# fpgaPower.net
KiCad netlist of a schematic drawn in Altium Designer
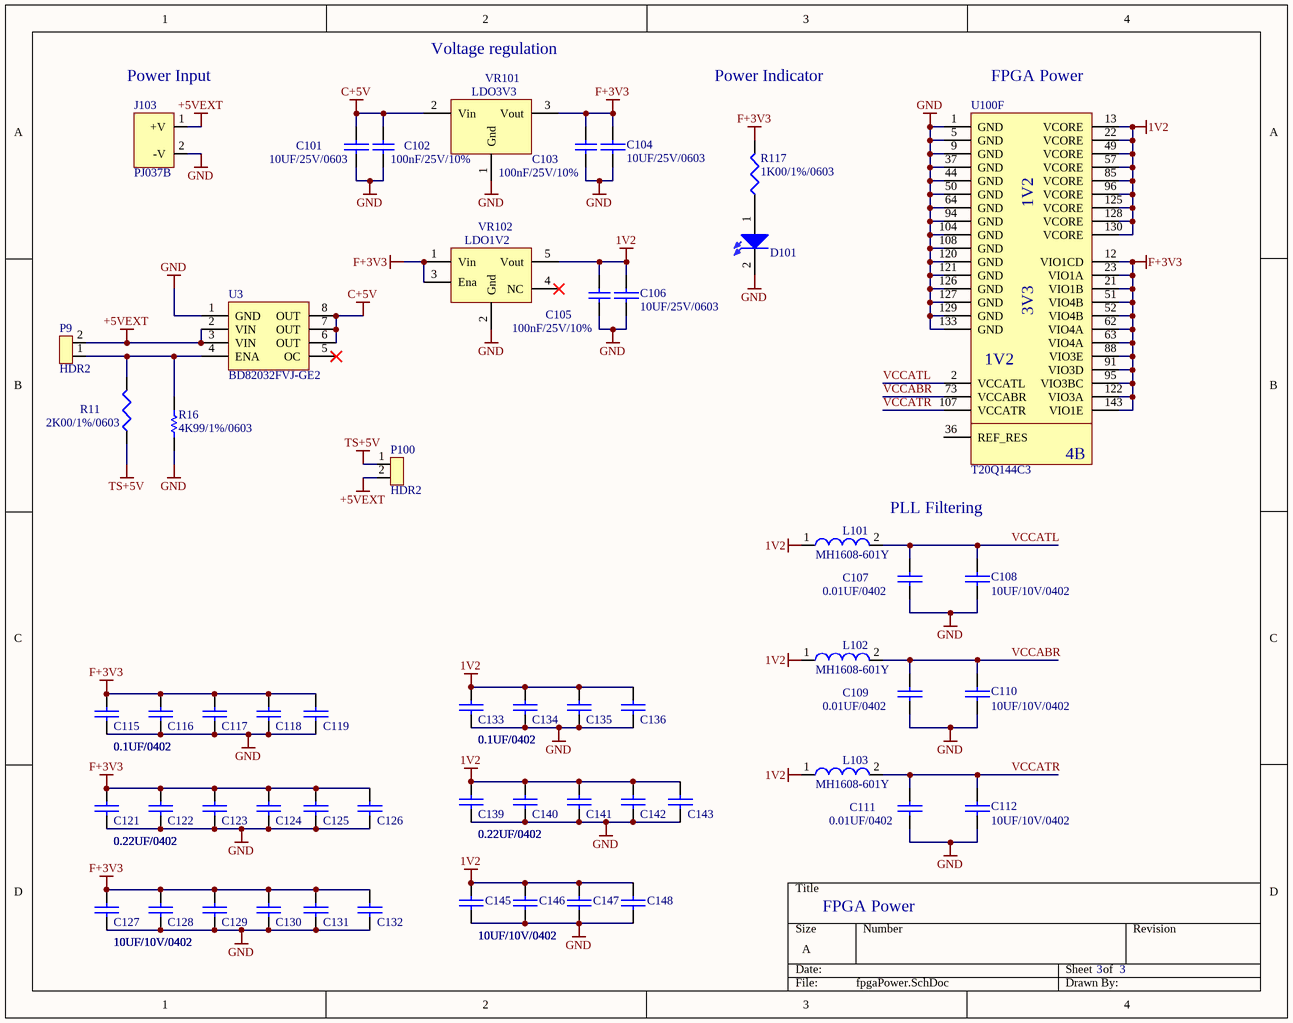
[diagram p0: fpgaPower.SchDoc]

(export (version "E")
  (design (tool "Eeschema 10.0.6"))
  (components
    (comp (ref "C101")
      (value "10UF/25V/0603")
      (footprint "0603")
      (description "10 µF ±20% 25V Ceramic Capacitor X5R 0603 (1608 Metric)")
      (fields (field (name "MFG") "Samsung"))
      (libsource (lib "Capacitors") (part "10UF/25V/0603"))
    )
    (comp (ref "C102")
      (value "100nF/25V/10%")
      (footprint "MY0603")
      (description "0.1µF ±10% 25V Ceramic Capacitor X7R 0603 (1608 Metric)")
      (fields (field (name "MFG") "AVX"))
      (libsource (lib "Capacitors") (part "CAP100NF25V"))
    )
    (comp (ref "C103")
      (value "100nF/25V/10%")
      (footprint "MY0603")
      (description "0.1µF ±10% 25V Ceramic Capacitor X7R 0603 (1608 Metric)")
      (fields (field (name "MFG") "AVX"))
      (libsource (lib "Capacitors") (part "CAP100NF25V"))
    )
    (comp (ref "C104")
      (value "10UF/25V/0603")
      (footprint "0603")
      (description "10 µF ±20% 25V Ceramic Capacitor X5R 0603 (1608 Metric)")
      (fields (field (name "MFG") "Samsung"))
      (libsource (lib "Capacitors") (part "10UF/25V/0603"))
    )
    (comp (ref "C105")
      (value "100nF/25V/10%")
      (footprint "MY0603")
      (description "0.1µF ±10% 25V Ceramic Capacitor X7R 0603 (1608 Metric)")
      (fields (field (name "MFG") "AVX"))
      (libsource (lib "Capacitors") (part "CAP100NF25V"))
    )
    (comp (ref "C106")
      (value "10UF/25V/0603")
      (footprint "0603")
      (description "10 µF ±20% 25V Ceramic Capacitor X5R 0603 (1608 Metric)")
      (fields (field (name "MFG") "Samsung"))
      (libsource (lib "Capacitors") (part "10UF/25V/0603"))
    )
    (comp (ref "C107")
      (value "0.01UF/0402")
      (footprint "0402")
      (description "±10% 16V Ceramic Capacitor X7R 0402 (1005 Metric)")
      (fields (field (name "MFG") "Cal-Chip"))
      (libsource (lib "Capacitors") (part "0.01UF/16vV/0402"))
    )
    (comp (ref "C108")
      (value "10UF/10V/0402")
      (footprint "0402")
      (description "±20% 10V Ceramic Capacitor X5R 0402 (1005 Metric)")
      (fields (field (name "MFG") "Samsung"))
      (libsource (lib "Capacitors") (part "10UF/10V/0402"))
    )
    (comp (ref "C109")
      (value "0.01UF/0402")
      (footprint "0402")
      (description "±10% 16V Ceramic Capacitor X7R 0402 (1005 Metric)")
      (fields (field (name "MFG") "Cal-Chip"))
      (libsource (lib "Capacitors") (part "0.01UF/16vV/0402"))
    )
    (comp (ref "C110")
      (value "10UF/10V/0402")
      (footprint "0402")
      (description "±20% 10V Ceramic Capacitor X5R 0402 (1005 Metric)")
      (fields (field (name "MFG") "Samsung"))
      (libsource (lib "Capacitors") (part "10UF/10V/0402"))
    )
    (comp (ref "C111")
      (value "0.01UF/0402")
      (footprint "0402")
      (description "±10% 16V Ceramic Capacitor X7R 0402 (1005 Metric)")
      (fields (field (name "MFG") "Cal-Chip"))
      (libsource (lib "Capacitors") (part "0.01UF/16vV/0402"))
    )
    (comp (ref "C112")
      (value "10UF/10V/0402")
      (footprint "0402")
      (description "±20% 10V Ceramic Capacitor X5R 0402 (1005 Metric)")
      (fields (field (name "MFG") "Samsung"))
      (libsource (lib "Capacitors") (part "10UF/10V/0402"))
    )
    (comp (ref "C115")
      (value "0.1UF/0402")
      (footprint "0402")
      (description "±10% 16V Ceramic Capacitor X7R 0402 (1005 Metric)")
      (fields (field (name "MFG") "TDK"))
      (libsource (lib "Capacitors") (part "0.1UF/16v/0402"))
    )
    (comp (ref "C116")
      (value "0.1UF/0402")
      (footprint "0402")
      (description "±10% 16V Ceramic Capacitor X7R 0402 (1005 Metric)")
      (fields (field (name "MFG") "TDK"))
      (libsource (lib "Capacitors") (part "0.1UF/16v/0402"))
    )
    (comp (ref "C117")
      (value "0.1UF/0402")
      (footprint "0402")
      (description "±10% 16V Ceramic Capacitor X7R 0402 (1005 Metric)")
      (fields (field (name "MFG") "TDK"))
      (libsource (lib "Capacitors") (part "0.1UF/16v/0402"))
    )
    (comp (ref "C118")
      (value "0.1UF/0402")
      (footprint "0402")
      (description "±10% 16V Ceramic Capacitor X7R 0402 (1005 Metric)")
      (fields (field (name "MFG") "TDK"))
      (libsource (lib "Capacitors") (part "0.1UF/16v/0402"))
    )
    (comp (ref "C119")
      (value "0.1UF/0402")
      (footprint "0402")
      (description "±10% 16V Ceramic Capacitor X7R 0402 (1005 Metric)")
      (fields (field (name "MFG") "TDK"))
      (libsource (lib "Capacitors") (part "0.1UF/16v/0402"))
    )
    (comp (ref "C121")
      (value "0.22UF/0402")
      (footprint "0402")
      (description "0.22 µF ±10% 25V Ceramic Capacitor X5R 0402 (1005 Metric)")
      (fields (field (name "MFG") "Yaego"))
      (libsource (lib "Capacitors") (part "0.22UF/0402"))
    )
    (comp (ref "C122")
      (value "0.22UF/0402")
      (footprint "0402")
      (description "0.22 µF ±10% 25V Ceramic Capacitor X5R 0402 (1005 Metric)")
      (fields (field (name "MFG") "Yaego"))
      (libsource (lib "Capacitors") (part "0.22UF/0402"))
    )
    (comp (ref "C123")
      (value "0.22UF/0402")
      (footprint "0402")
      (description "0.22 µF ±10% 25V Ceramic Capacitor X5R 0402 (1005 Metric)")
      (fields (field (name "MFG") "Yaego"))
      (libsource (lib "Capacitors") (part "0.22UF/0402"))
    )
    (comp (ref "C124")
      (value "0.22UF/0402")
      (footprint "0402")
      (description "0.22 µF ±10% 25V Ceramic Capacitor X5R 0402 (1005 Metric)")
      (fields (field (name "MFG") "Yaego"))
      (libsource (lib "Capacitors") (part "0.22UF/0402"))
    )
    (comp (ref "C125")
      (value "0.22UF/0402")
      (footprint "0402")
      (description "0.22 µF ±10% 25V Ceramic Capacitor X5R 0402 (1005 Metric)")
      (fields (field (name "MFG") "Yaego"))
      (libsource (lib "Capacitors") (part "0.22UF/0402"))
    )
    (comp (ref "C126")
      (value "0.22UF/0402")
      (footprint "0402")
      (description "0.22 µF ±10% 25V Ceramic Capacitor X5R 0402 (1005 Metric)")
      (fields (field (name "MFG") "Yaego"))
      (libsource (lib "Capacitors") (part "0.22UF/0402"))
    )
    (comp (ref "C127")
      (value "10UF/10V/0402")
      (footprint "0402")
      (description "±20% 10V Ceramic Capacitor X5R 0402 (1005 Metric)")
      (fields (field (name "MFG") "Samsung"))
      (libsource (lib "Capacitors") (part "10UF/10V/0402"))
    )
    (comp (ref "C128")
      (value "10UF/10V/0402")
      (footprint "0402")
      (description "±20% 10V Ceramic Capacitor X5R 0402 (1005 Metric)")
      (fields (field (name "MFG") "Samsung"))
      (libsource (lib "Capacitors") (part "10UF/10V/0402"))
    )
    (comp (ref "C129")
      (value "10UF/10V/0402")
      (footprint "0402")
      (description "±20% 10V Ceramic Capacitor X5R 0402 (1005 Metric)")
      (fields (field (name "MFG") "Samsung"))
      (libsource (lib "Capacitors") (part "10UF/10V/0402"))
    )
    (comp (ref "C130")
      (value "10UF/10V/0402")
      (footprint "0402")
      (description "±20% 10V Ceramic Capacitor X5R 0402 (1005 Metric)")
      (fields (field (name "MFG") "Samsung"))
      (libsource (lib "Capacitors") (part "10UF/10V/0402"))
    )
    (comp (ref "C131")
      (value "10UF/10V/0402")
      (footprint "0402")
      (description "±20% 10V Ceramic Capacitor X5R 0402 (1005 Metric)")
      (fields (field (name "MFG") "Samsung"))
      (libsource (lib "Capacitors") (part "10UF/10V/0402"))
    )
    (comp (ref "C132")
      (value "10UF/10V/0402")
      (footprint "0402")
      (description "±20% 10V Ceramic Capacitor X5R 0402 (1005 Metric)")
      (fields (field (name "MFG") "Samsung"))
      (libsource (lib "Capacitors") (part "10UF/10V/0402"))
    )
    (comp (ref "C133")
      (value "0.1UF/0402")
      (footprint "0402")
      (description "±10% 16V Ceramic Capacitor X7R 0402 (1005 Metric)")
      (fields (field (name "MFG") "TDK"))
      (libsource (lib "Capacitors") (part "0.1UF/16v/0402"))
    )
    (comp (ref "C134")
      (value "0.1UF/0402")
      (footprint "0402")
      (description "±10% 16V Ceramic Capacitor X7R 0402 (1005 Metric)")
      (fields (field (name "MFG") "TDK"))
      (libsource (lib "Capacitors") (part "0.1UF/16v/0402"))
    )
    (comp (ref "C135")
      (value "0.1UF/0402")
      (footprint "0402")
      (description "±10% 16V Ceramic Capacitor X7R 0402 (1005 Metric)")
      (fields (field (name "MFG") "TDK"))
      (libsource (lib "Capacitors") (part "0.1UF/16v/0402"))
    )
    (comp (ref "C136")
      (value "0.1UF/0402")
      (footprint "0402")
      (description "±10% 16V Ceramic Capacitor X7R 0402 (1005 Metric)")
      (fields (field (name "MFG") "TDK"))
      (libsource (lib "Capacitors") (part "0.1UF/16v/0402"))
    )
    (comp (ref "C139")
      (value "0.22UF/0402")
      (footprint "0402")
      (description "0.22 µF ±10% 25V Ceramic Capacitor X5R 0402 (1005 Metric)")
      (fields (field (name "MFG") "Yaego"))
      (libsource (lib "Capacitors") (part "0.22UF/0402"))
    )
    (comp (ref "C140")
      (value "0.22UF/0402")
      (footprint "0402")
      (description "0.22 µF ±10% 25V Ceramic Capacitor X5R 0402 (1005 Metric)")
      (fields (field (name "MFG") "Yaego"))
      (libsource (lib "Capacitors") (part "0.22UF/0402"))
    )
    (comp (ref "C141")
      (value "0.22UF/0402")
      (footprint "0402")
      (description "0.22 µF ±10% 25V Ceramic Capacitor X5R 0402 (1005 Metric)")
      (fields (field (name "MFG") "Yaego"))
      (libsource (lib "Capacitors") (part "0.22UF/0402"))
    )
    (comp (ref "C142")
      (value "0.22UF/0402")
      (footprint "0402")
      (description "0.22 µF ±10% 25V Ceramic Capacitor X5R 0402 (1005 Metric)")
      (fields (field (name "MFG") "Yaego"))
      (libsource (lib "Capacitors") (part "0.22UF/0402"))
    )
    (comp (ref "C143")
      (value "0.22UF/0402")
      (footprint "0402")
      (description "0.22 µF ±10% 25V Ceramic Capacitor X5R 0402 (1005 Metric)")
      (fields (field (name "MFG") "Yaego"))
      (libsource (lib "Capacitors") (part "0.22UF/0402"))
    )
    (comp (ref "C145")
      (value "10UF/10V/0402")
      (footprint "0402")
      (description "±20% 10V Ceramic Capacitor X5R 0402 (1005 Metric)")
      (fields (field (name "MFG") "Samsung"))
      (libsource (lib "Capacitors") (part "10UF/10V/0402"))
    )
    (comp (ref "C146")
      (value "10UF/10V/0402")
      (footprint "0402")
      (description "±20% 10V Ceramic Capacitor X5R 0402 (1005 Metric)")
      (fields (field (name "MFG") "Samsung"))
      (libsource (lib "Capacitors") (part "10UF/10V/0402"))
    )
    (comp (ref "C147")
      (value "10UF/10V/0402")
      (footprint "0402")
      (description "±20% 10V Ceramic Capacitor X5R 0402 (1005 Metric)")
      (fields (field (name "MFG") "Samsung"))
      (libsource (lib "Capacitors") (part "10UF/10V/0402"))
    )
    (comp (ref "C148")
      (value "10UF/10V/0402")
      (footprint "0402")
      (description "±20% 10V Ceramic Capacitor X5R 0402 (1005 Metric)")
      (fields (field (name "MFG") "Samsung"))
      (libsource (lib "Capacitors") (part "10UF/10V/0402"))
    )
    (comp (ref "D101")
      (value "LTST-C191KGKT")
      (footprint "LED0603")
      (description "Green 571nm LED Indication - Discrete 2V 0603 (1608 Metric)")
      (fields (field (name "MFG") "Liteon"))
      (libsource (lib "MiscSemi") (part "LTST-C191KGKT"))
    )
    (comp (ref "J103")
      (value "PJ037B")
      (footprint "PJ037B")
      (description "Power Barrel Connector Jack 2.50mm ID (0.098\"), 5.50mm OD (0.217\") Through Hole, Right Angle")
      (fields (field (name "MFG") "CUI"))
      (libsource (lib "APN") (part "PJ037B"))
    )
    (comp (ref "L101")
      (value "MH1608-601Y")
      (footprint "0603")
      (description "600 Ohms @ 100 MHz 1 Power, Signal Line Ferrite Bead 0603 (1608 Metric) 1A 200mOhm")
      (fields (field (name "MFG") "Bourns"))
      (libsource (lib "Misc") (part "MH1608-601Y"))
    )
    (comp (ref "L102")
      (value "MH1608-601Y")
      (footprint "0603")
      (description "600 Ohms @ 100 MHz 1 Power, Signal Line Ferrite Bead 0603 (1608 Metric) 1A 200mOhm")
      (fields (field (name "MFG") "Bourns"))
      (libsource (lib "Misc") (part "MH1608-601Y"))
    )
    (comp (ref "L103")
      (value "MH1608-601Y")
      (footprint "0603")
      (description "600 Ohms @ 100 MHz 1 Power, Signal Line Ferrite Bead 0603 (1608 Metric) 1A 200mOhm")
      (fields (field (name "MFG") "Bourns"))
      (libsource (lib "Misc") (part "MH1608-601Y"))
    )
    (comp (ref "P9") (value "HDR2") (footprint "HDR2") (libsource (lib "C64Interface") (part "HDR2")))
    (comp (ref "P100") (value "HDR2") (footprint "HDR2") (libsource (lib "Connectors") (part "HDR2")))
    (comp (ref "R11")
      (value "2K00/1%/0603")
      (footprint "0603")
      (description "2 kOhms ±1% 0.1W, 1/10W Chip Resistor 0603 (1608 Metric) Moisture Resistant Thick Film")
      (fields (field (name "MFG") "Yeago"))
      (libsource (lib "Resistors") (part "2K00/1%/0603"))
    )
    (comp (ref "R16")
      (value "4K99/1%/0603")
      (footprint "0603")
      (description "4.99k Ohm ±1% 0.1W, 1/10W Chip Resistor 0603 (1608 Metric) Moisture Resistant Thick Film")
      (fields (field (name "MFG") "Yageo"))
      (libsource (lib "Resistors") (part "RES4K99"))
    )
    (comp (ref "R117")
      (value "1K00/1%/0603")
      (footprint "0603")
      (description "1 kOhms ±1% 0.1W, 1/10W Chip Resistor 0603 (1608 Metric) Moisture Resistant Thick Film")
      (fields (field (name "MFG") "Yeago"))
      (libsource (lib "Resistors") (part "1K00/1%/0603"))
    )
    (comp (ref "U3")
      (value "BD82032FVJ-GE2")
      (footprint "TSSOP8-A")
      (description "Power Switch/Driver 1:1 N-Channel 2A 8-TSSOP-BJ")
      (fields (field (name "MFG") "Rohm"))
      (libsource (lib "Power") (part "BD82032FVJ-GE2"))
    )
    (comp (ref "U100")
      (value "T20Q144C3")
      (footprint "LQFP144")
      (description "Trion® Field Programmable Gate Array (FPGA) IC 97 1044 19728 144-LQFP")
      (fields (field (name "MFG") "Efinix"))
      (libsource (lib "DigitalIC") (part "T20Q144C3"))
    )
    (comp (ref "VR101")
      (value "LDO3V3")
      (footprint "DPAK")
      (description "Linear Voltage Regulator IC Positive Fixed 1 Output 1.5A DPAK")
      (fields (field (name "MFG") "STM"))
      (libsource (lib "Power") (part "LDO3V3"))
    )
    (comp (ref "VR102")
      (value "LDO1V2")
      (footprint "SOT23-5")
      (description "Linear Voltage Regulator IC Positive Fixed 1 Output 1.5A DPAK")
      (fields (field (name "MFG") "On Semi"))
      (libsource (lib "Power") (part "LDO1V2"))
    )
  )
  (nets
    (net (code "1") (name "+5VEXT") (class "Default")
      (node (ref "J103") (pin "1") (pinfunction "+V_1") (pintype "passive"))
      (node (ref "P100") (pin "2") (pintype "passive"))
      (node (ref "P9") (pin "2") (pintype "passive"))
      (node (ref "U3") (pin "2") (pinfunction "VIN_2") (pintype "passive"))
      (node (ref "U3") (pin "3") (pinfunction "VIN_3") (pintype "passive"))
    )
    (net (code "2") (name "/VCCABR") (class "Default")
      (node (ref "C109") (pin "1") (pintype "passive"))
      (node (ref "C110") (pin "1") (pintype "passive"))
      (node (ref "L102") (pin "2") (pinfunction "2_2") (pintype "passive"))
      (node (ref "U100") (pin "73") (pinfunction "VCCABR_73") (pintype "power_in"))
    )
    (net (code "3") (name "/VCCATL") (class "Default")
      (node (ref "C107") (pin "1") (pintype "passive"))
      (node (ref "C108") (pin "1") (pintype "passive"))
      (node (ref "L101") (pin "2") (pinfunction "2_2") (pintype "passive"))
      (node (ref "U100") (pin "2") (pinfunction "VCCATL_2") (pintype "power_in"))
    )
    (net (code "4") (name "/VCCATR") (class "Default")
      (node (ref "C111") (pin "1") (pintype "passive"))
      (node (ref "C112") (pin "1") (pintype "passive"))
      (node (ref "L103") (pin "2") (pinfunction "2_2") (pintype "passive"))
      (node (ref "U100") (pin "107") (pinfunction "VCCATR_107") (pintype "power_in"))
    )
    (net (code "5") (name "1V2") (class "Default")
      (node (ref "C105") (pin "2") (pinfunction "2_2") (pintype "passive"))
      (node (ref "C106") (pin "1") (pintype "passive"))
      (node (ref "C133") (pin "1") (pintype "passive"))
      (node (ref "C134") (pin "1") (pintype "passive"))
      (node (ref "C135") (pin "1") (pintype "passive"))
      (node (ref "C136") (pin "1") (pintype "passive"))
      (node (ref "C139") (pin "1") (pintype "passive"))
      (node (ref "C140") (pin "1") (pintype "passive"))
      (node (ref "C141") (pin "1") (pintype "passive"))
      (node (ref "C142") (pin "1") (pintype "passive"))
      (node (ref "C143") (pin "1") (pintype "passive"))
      (node (ref "C145") (pin "1") (pintype "passive"))
      (node (ref "C146") (pin "1") (pintype "passive"))
      (node (ref "C147") (pin "1") (pintype "passive"))
      (node (ref "C148") (pin "1") (pintype "passive"))
      (node (ref "L101") (pin "1") (pinfunction "1_1") (pintype "passive"))
      (node (ref "L102") (pin "1") (pinfunction "1_1") (pintype "passive"))
      (node (ref "L103") (pin "1") (pinfunction "1_1") (pintype "passive"))
      (node (ref "U100") (pin "125") (pinfunction "VCORE_125") (pintype "power_in"))
      (node (ref "U100") (pin "128") (pinfunction "VCORE_128") (pintype "power_in"))
      (node (ref "U100") (pin "13") (pinfunction "VCORE_13") (pintype "power_in"))
      (node (ref "U100") (pin "130") (pinfunction "VCORE_130") (pintype "power_in"))
      (node (ref "U100") (pin "22") (pinfunction "VCORE_22") (pintype "power_in"))
      (node (ref "U100") (pin "49") (pinfunction "VCORE_49") (pintype "power_in"))
      (node (ref "U100") (pin "57") (pinfunction "VCORE_57") (pintype "power_in"))
      (node (ref "U100") (pin "85") (pinfunction "VCORE_85") (pintype "power_in"))
      (node (ref "U100") (pin "96") (pinfunction "VCORE_96") (pintype "power_in"))
      (node (ref "VR102") (pin "5") (pinfunction "Vout_5") (pintype "passive"))
    )
    (net (code "6") (name "C+5V") (class "Default")
      (node (ref "C101") (pin "1") (pintype "passive"))
      (node (ref "C102") (pin "2") (pinfunction "2_2") (pintype "passive"))
      (node (ref "U3") (pin "6") (pinfunction "OUT_6") (pintype "passive"))
      (node (ref "U3") (pin "7") (pinfunction "OUT_7") (pintype "passive"))
      (node (ref "U3") (pin "8") (pinfunction "OUT_8") (pintype "passive"))
      (node (ref "VR101") (pin "2") (pinfunction "Vin_2") (pintype "power_in"))
    )
    (net (code "7") (name "F+3V3") (class "Default")
      (node (ref "C103") (pin "2") (pinfunction "2_2") (pintype "passive"))
      (node (ref "C104") (pin "1") (pintype "passive"))
      (node (ref "C115") (pin "1") (pintype "passive"))
      (node (ref "C116") (pin "1") (pintype "passive"))
      (node (ref "C117") (pin "1") (pintype "passive"))
      (node (ref "C118") (pin "1") (pintype "passive"))
      (node (ref "C119") (pin "1") (pintype "passive"))
      (node (ref "C121") (pin "1") (pintype "passive"))
      (node (ref "C122") (pin "1") (pintype "passive"))
      (node (ref "C123") (pin "1") (pintype "passive"))
      (node (ref "C124") (pin "1") (pintype "passive"))
      (node (ref "C125") (pin "1") (pintype "passive"))
      (node (ref "C126") (pin "1") (pintype "passive"))
      (node (ref "C127") (pin "1") (pintype "passive"))
      (node (ref "C128") (pin "1") (pintype "passive"))
      (node (ref "C129") (pin "1") (pintype "passive"))
      (node (ref "C130") (pin "1") (pintype "passive"))
      (node (ref "C131") (pin "1") (pintype "passive"))
      (node (ref "C132") (pin "1") (pintype "passive"))
      (node (ref "R117") (pin "2") (pintype "passive"))
      (node (ref "U100") (pin "12") (pinfunction "VIO1CD_12") (pintype "power_in"))
      (node (ref "U100") (pin "122") (pinfunction "VIO3A_122") (pintype "power_in"))
      (node (ref "U100") (pin "143") (pinfunction "VIO1E_143") (pintype "power_in"))
      (node (ref "U100") (pin "21") (pinfunction "VIO1B_21") (pintype "power_in"))
      (node (ref "U100") (pin "23") (pinfunction "VIO1A_23") (pintype "power_in"))
      (node (ref "U100") (pin "51") (pinfunction "VIO4B_51") (pintype "power_in"))
      (node (ref "U100") (pin "52") (pinfunction "VIO4B_52") (pintype "power_in"))
      (node (ref "U100") (pin "62") (pinfunction "VIO4A_62") (pintype "power_in"))
      (node (ref "U100") (pin "63") (pinfunction "VIO4A_63") (pintype "power_in"))
      (node (ref "U100") (pin "88") (pinfunction "VIO3E_88") (pintype "power_in"))
      (node (ref "U100") (pin "91") (pinfunction "VIO3D_91") (pintype "power_in"))
      (node (ref "U100") (pin "95") (pinfunction "VIO3BC_95") (pintype "power_in"))
      (node (ref "VR101") (pin "3") (pinfunction "Vout_3") (pintype "power_in"))
      (node (ref "VR102") (pin "1") (pinfunction "Vin_1") (pintype "power_in"))
      (node (ref "VR102") (pin "3") (pinfunction "Ena_3") (pintype "power_in"))
    )
    (net (code "8") (name "GND") (class "Default")
      (node (ref "C101") (pin "2") (pintype "passive"))
      (node (ref "C102") (pin "1") (pinfunction "1_1") (pintype "passive"))
      (node (ref "C103") (pin "1") (pinfunction "1_1") (pintype "passive"))
      (node (ref "C104") (pin "2") (pintype "passive"))
      (node (ref "C105") (pin "1") (pinfunction "1_1") (pintype "passive"))
      (node (ref "C106") (pin "2") (pintype "passive"))
      (node (ref "C107") (pin "2") (pintype "passive"))
      (node (ref "C108") (pin "2") (pintype "passive"))
      (node (ref "C109") (pin "2") (pintype "passive"))
      (node (ref "C110") (pin "2") (pintype "passive"))
      (node (ref "C111") (pin "2") (pintype "passive"))
      (node (ref "C112") (pin "2") (pintype "passive"))
      (node (ref "C115") (pin "2") (pintype "passive"))
      (node (ref "C116") (pin "2") (pintype "passive"))
      (node (ref "C117") (pin "2") (pintype "passive"))
      (node (ref "C118") (pin "2") (pintype "passive"))
      (node (ref "C119") (pin "2") (pintype "passive"))
      (node (ref "C121") (pin "2") (pintype "passive"))
      (node (ref "C122") (pin "2") (pintype "passive"))
      (node (ref "C123") (pin "2") (pintype "passive"))
      (node (ref "C124") (pin "2") (pintype "passive"))
      (node (ref "C125") (pin "2") (pintype "passive"))
      (node (ref "C126") (pin "2") (pintype "passive"))
      (node (ref "C127") (pin "2") (pintype "passive"))
      (node (ref "C128") (pin "2") (pintype "passive"))
      (node (ref "C129") (pin "2") (pintype "passive"))
      (node (ref "C130") (pin "2") (pintype "passive"))
      (node (ref "C131") (pin "2") (pintype "passive"))
      (node (ref "C132") (pin "2") (pintype "passive"))
      (node (ref "C133") (pin "2") (pintype "passive"))
      (node (ref "C134") (pin "2") (pintype "passive"))
      (node (ref "C135") (pin "2") (pintype "passive"))
      (node (ref "C136") (pin "2") (pintype "passive"))
      (node (ref "C139") (pin "2") (pintype "passive"))
      (node (ref "C140") (pin "2") (pintype "passive"))
      (node (ref "C141") (pin "2") (pintype "passive"))
      (node (ref "C142") (pin "2") (pintype "passive"))
      (node (ref "C143") (pin "2") (pintype "passive"))
      (node (ref "C145") (pin "2") (pintype "passive"))
      (node (ref "C146") (pin "2") (pintype "passive"))
      (node (ref "C147") (pin "2") (pintype "passive"))
      (node (ref "C148") (pin "2") (pintype "passive"))
      (node (ref "D101") (pin "2") (pinfunction "K_2") (pintype "passive"))
      (node (ref "J103") (pin "2") (pinfunction "-V_2") (pintype "passive"))
      (node (ref "R16") (pin "1") (pinfunction "1_1") (pintype "passive"))
      (node (ref "U100") (pin "1") (pinfunction "GND_1") (pintype "power_in"))
      (node (ref "U100") (pin "104") (pinfunction "GND_104") (pintype "power_in"))
      (node (ref "U100") (pin "108") (pinfunction "GND_108") (pintype "power_in"))
      (node (ref "U100") (pin "120") (pinfunction "GND_120") (pintype "power_in"))
      (node (ref "U100") (pin "121") (pinfunction "GND_121") (pintype "power_in"))
      (node (ref "U100") (pin "126") (pinfunction "GND_126") (pintype "power_in"))
      (node (ref "U100") (pin "127") (pinfunction "GND_127") (pintype "power_in"))
      (node (ref "U100") (pin "129") (pinfunction "GND_129") (pintype "power_in"))
      (node (ref "U100") (pin "133") (pinfunction "GND_133") (pintype "power_in"))
      (node (ref "U100") (pin "37") (pinfunction "GND_37") (pintype "power_in"))
      (node (ref "U100") (pin "44") (pinfunction "GND_44") (pintype "power_in"))
      (node (ref "U100") (pin "5") (pinfunction "GND_5") (pintype "power_in"))
      (node (ref "U100") (pin "50") (pinfunction "GND_50") (pintype "power_in"))
      (node (ref "U100") (pin "64") (pinfunction "GND_64") (pintype "power_in"))
      (node (ref "U100") (pin "9") (pinfunction "GND_9") (pintype "power_in"))
      (node (ref "U100") (pin "94") (pinfunction "GND_94") (pintype "power_in"))
      (node (ref "U3") (pin "1") (pinfunction "GND_1") (pintype "passive"))
      (node (ref "VR101") (pin "1") (pinfunction "Gnd_1") (pintype "power_in"))
      (node (ref "VR102") (pin "2") (pinfunction "Gnd_2") (pintype "power_in"))
    )
    (net (code "9") (name "Net-(D101-A)") (class "Default")
      (node (ref "D101") (pin "1") (pinfunction "A_1") (pintype "passive"))
      (node (ref "R117") (pin "1") (pintype "passive"))
    )
    (net (code "10") (name "Net-(U3-ENA)") (class "Default")
      (node (ref "P9") (pin "1") (pintype "passive"))
      (node (ref "R11") (pin "2") (pintype "passive"))
      (node (ref "R16") (pin "2") (pinfunction "2_2") (pintype "passive"))
      (node (ref "U3") (pin "4") (pinfunction "ENA_4") (pintype "passive"))
    )
    (net (code "11") (name "TS+5V") (class "Default")
      (node (ref "P100") (pin "1") (pintype "passive"))
      (node (ref "R11") (pin "1") (pintype "passive"))
    )
    (net (code "12") (name "unconnected-(U3-OC-Pad5)") (class "Default")
      (node (ref "U3") (pin "5") (pinfunction "OC_5") (pintype "passive+no_connect"))
    )
    (net (code "13") (name "unconnected-(U100F-REF_RES-Pad36)") (class "Default")
      (node (ref "U100") (pin "36") (pinfunction "REF_RES_36") (pintype "passive"))
    )
    (net (code "14") (name "unconnected-(VR102-NC-Pad4)") (class "Default")
      (node (ref "VR102") (pin "4") (pinfunction "NC_4") (pintype "passive+no_connect"))
    )
  )
)
